# nRF24L01-Chip-v13.net
KiCad netlist of a schematic drawn in EAGLE
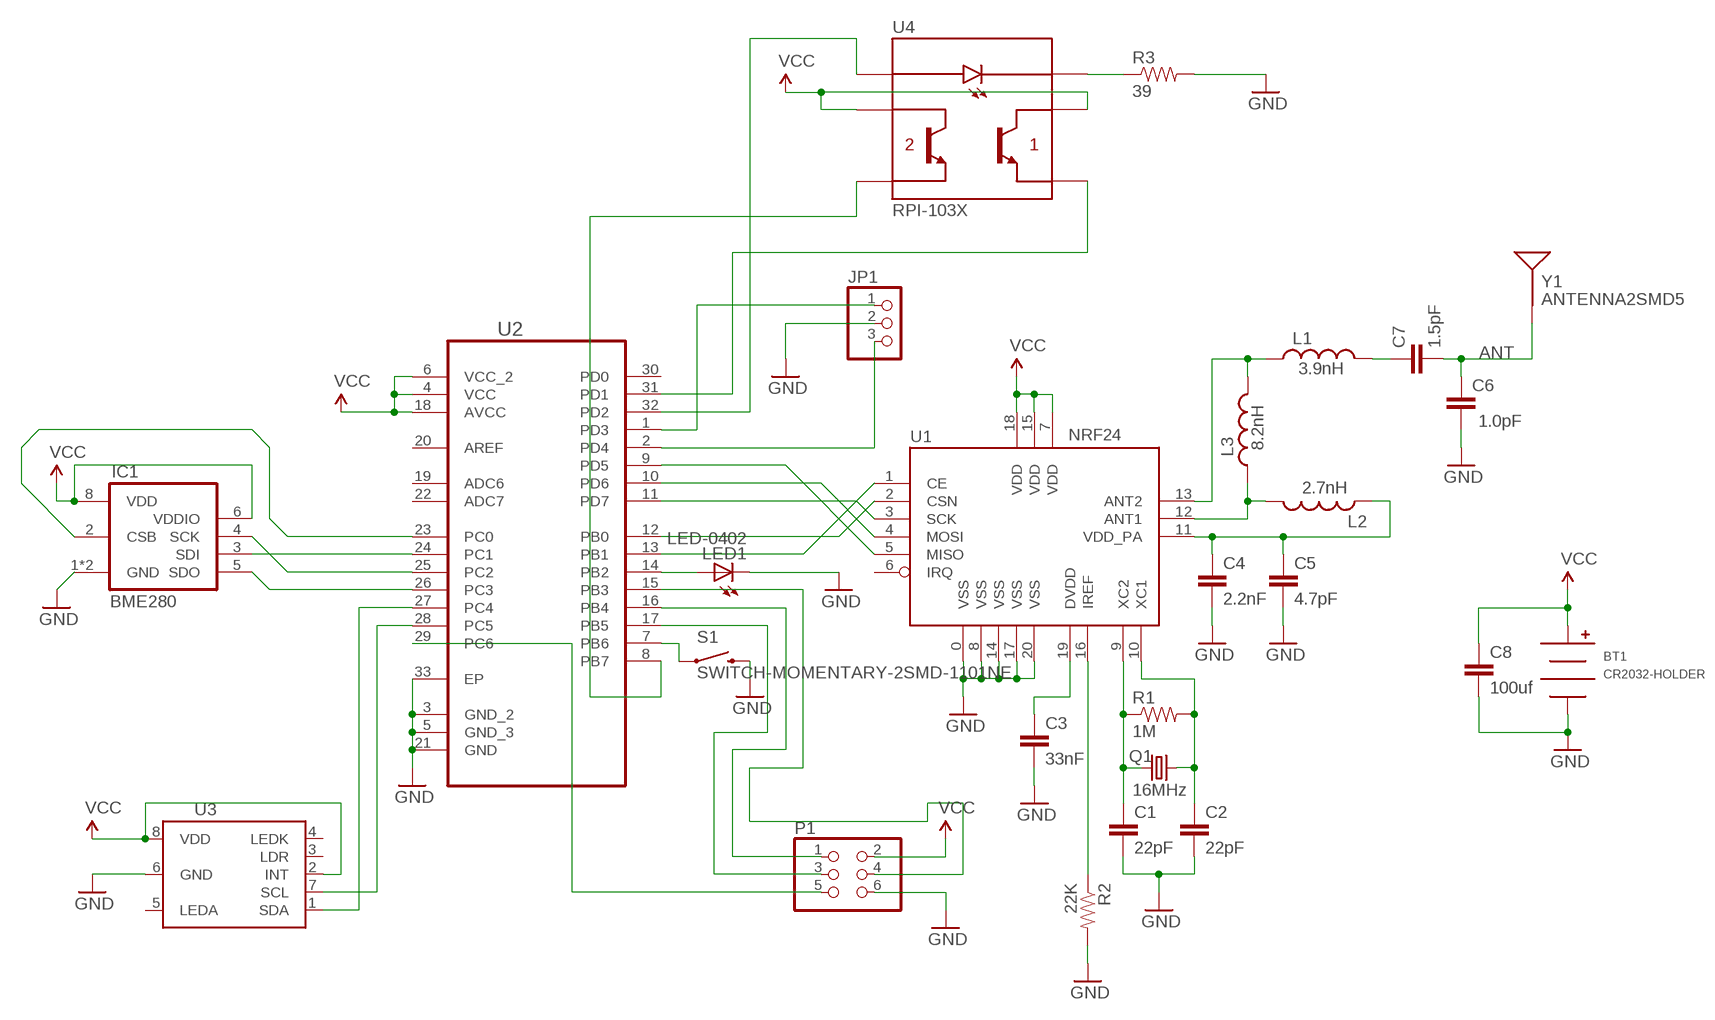
[diagram p0: schematic, sheet 1]

(export (version "E")
  (design (tool "Eeschema 10.0.6"))
  (components
    (comp (ref "BT1")
      (value "CR2032-HOLDER")
      (footprint "eagle-import:CH28-2032LF")
      (libsource (lib "eagle-import") (part "CR2032-HOLDER"))
    )
    (comp (ref "C1")
      (value "22pF")
      (footprint "eagle-import:0402-CAP")
      (libsource (lib "eagle-import") (part "CAP0402-CAP"))
    )
    (comp (ref "C2")
      (value "22pF")
      (footprint "eagle-import:0402-CAP")
      (libsource (lib "eagle-import") (part "CAP0402-CAP"))
    )
    (comp (ref "C3")
      (value "33nF")
      (footprint "eagle-import:0402-CAP")
      (libsource (lib "eagle-import") (part "CAP0402-CAP"))
    )
    (comp (ref "C4")
      (value "2.2nF")
      (footprint "eagle-import:0402-CAP")
      (libsource (lib "eagle-import") (part "CAP0402-CAP"))
    )
    (comp (ref "C5")
      (value "4.7pF")
      (footprint "eagle-import:0402-CAP")
      (libsource (lib "eagle-import") (part "CAP0402-CAP"))
    )
    (comp (ref "C6")
      (value "1.0pF")
      (footprint "eagle-import:0402-CAP")
      (libsource (lib "eagle-import") (part "CAP0402-CAP"))
    )
    (comp (ref "C7")
      (value "1.5pF")
      (footprint "eagle-import:0402-CAP")
      (libsource (lib "eagle-import") (part "CAP0402-CAP"))
    )
    (comp (ref "C8")
      (value "100uf")
      (footprint "eagle-import:1206")
      (libsource (lib "eagle-import") (part "SparkFun-Capacitors_CAP1206"))
    )
    (comp (ref "IC1")
      (value "BME280")
      (footprint "eagle-import:BME280")
      (libsource (lib "eagle-import") (part "BME280"))
    )
    (comp (ref "JP1")
      (value "PINHD-1X31X03_SMT")
      (footprint "eagle-import:1X03_SMT")
      (libsource (lib "eagle-import") (part "PINHD-1X31X03_SMT"))
    )
    (comp (ref "L1")
      (value "3.9nH")
      (footprint "eagle-import:C0402")
      (libsource (lib "eagle-import") (part "INDUCTOR0402"))
    )
    (comp (ref "L2")
      (value "2.7nH")
      (footprint "eagle-import:C0402")
      (libsource (lib "eagle-import") (part "INDUCTOR0402"))
    )
    (comp (ref "L3")
      (value "8.2nH")
      (footprint "eagle-import:C0402")
      (libsource (lib "eagle-import") (part "INDUCTOR0402"))
    )
    (comp (ref "LED1")
      (value "LED-0402")
      (footprint "eagle-import:0402-LED")
      (libsource (lib "eagle-import") (part "LED-0402"))
    )
    (comp (ref "P1")
      (value "PINHD-2X3SMT")
      (footprint "eagle-import:2X03_SMT")
      (libsource (lib "eagle-import") (part "PINHD-2X3SMT"))
    )
    (comp (ref "Q1")
      (value "16MHz")
      (footprint "eagle-import:CRYSTAL-SMD-5X3")
      (libsource (lib "eagle-import") (part "CRYSTAL5X3"))
    )
    (comp (ref "R1")
      (value "1M")
      (footprint "eagle-import:0402-RES")
      (libsource (lib "eagle-import") (part "RESISTOR0402-RES"))
    )
    (comp (ref "R2")
      (value "22K")
      (footprint "eagle-import:0402-RES")
      (libsource (lib "eagle-import") (part "RESISTOR0402-RES"))
    )
    (comp (ref "R3")
      (value "39")
      (footprint "eagle-import:0402-RES")
      (libsource (lib "eagle-import") (part "RESISTOR0402-RES"))
    )
    (comp (ref "S1")
      (value "SWITCH-MOMENTARY-2SMD-1101NE")
      (footprint "eagle-import:TACTILE-SWITCH-1101NE")
      (libsource (lib "eagle-import") (part "SWITCH-MOMENTARY-2SMD-1101NE"))
    )
    (comp (ref "U1")
      (value "NRF24")
      (footprint "eagle-import:QFN20_ALT1")
      (libsource (lib "eagle-import") (part "NRF24L01ALT1"))
    )
    (comp (ref "U2")
      (value "ATMEGA328P-MU")
      (footprint "eagle-import:QFN50P500X500X100-33N")
      (libsource (lib "eagle-import") (part "ATMEGA328P-MU"))
    )
    (comp (ref "U3")
      (value "APDS-9960")
      (footprint "eagle-import:APDS-9960")
      (libsource (lib "eagle-import") (part "APDS-9960"))
    )
    (comp (ref "U4")
      (value "RPI-103X")
      (footprint "eagle-import:RPI-103X")
      (libsource (lib "eagle-import") (part "RPI-103X"))
    )
    (comp (ref "Y1")
      (value "ANTENNA2SMD5")
      (footprint "eagle-import:ANTENNA-CHIP5")
      (libsource (lib "eagle-import") (part "ANTENNA2SMD5"))
    )
  )
  (nets
    (net (code "1") (name "/ANT") (class "Default")
      (node (ref "C6") (pin "2") (pinfunction "2_2") (pintype "passive"))
      (node (ref "C7") (pin "2") (pinfunction "2_2") (pintype "passive"))
      (node (ref "Y1") (pin "FEED") (pinfunction "SIGNAL_FEED") (pintype "bidirectional"))
    )
    (net (code "2") (name "GND") (class "Default")
      (node (ref "BT1") (pin "NEG") (pinfunction "NEG_NEG") (pintype "bidirectional"))
      (node (ref "C1") (pin "2") (pinfunction "2_2") (pintype "passive"))
      (node (ref "C2") (pin "2") (pinfunction "2_2") (pintype "passive"))
      (node (ref "C3") (pin "2") (pinfunction "2_2") (pintype "passive"))
      (node (ref "C4") (pin "2") (pinfunction "2_2") (pintype "passive"))
      (node (ref "C5") (pin "2") (pinfunction "2_2") (pintype "passive"))
      (node (ref "C6") (pin "1") (pinfunction "1_1") (pintype "passive"))
      (node (ref "C8") (pin "2") (pinfunction "2_2") (pintype "passive"))
      (node (ref "IC1") (pin "1") (pinfunction "GND_1") (pintype "power_in"))
      (node (ref "IC1") (pin "7") (pinfunction "GND_7") (pintype "power_in"))
      (node (ref "JP1") (pin "2") (pinfunction "2_2") (pintype "passive"))
      (node (ref "LED1") (pin "C") (pinfunction "C_C") (pintype "passive"))
      (node (ref "P1") (pin "6") (pinfunction "6_6") (pintype "passive"))
      (node (ref "R2") (pin "2") (pinfunction "2_2") (pintype "passive"))
      (node (ref "R3") (pin "2") (pinfunction "2_2") (pintype "passive"))
      (node (ref "S1") (pin "2") (pinfunction "2_2") (pintype "passive"))
      (node (ref "U1") (pin "0") (pinfunction "VSS_0") (pintype "power_in"))
      (node (ref "U1") (pin "14") (pinfunction "VSS_14") (pintype "power_in"))
      (node (ref "U1") (pin "17") (pinfunction "VSS_17") (pintype "power_in"))
      (node (ref "U1") (pin "20") (pinfunction "VSS_20") (pintype "power_in"))
      (node (ref "U1") (pin "8") (pinfunction "VSS_8") (pintype "power_in"))
      (node (ref "U2") (pin "21") (pinfunction "GND_21") (pintype "passive"))
      (node (ref "U2") (pin "3") (pinfunction "GND_2_3") (pintype "passive"))
      (node (ref "U2") (pin "33") (pinfunction "EP_33") (pintype "passive"))
      (node (ref "U2") (pin "5") (pinfunction "GND_3_5") (pintype "passive"))
      (node (ref "U3") (pin "6") (pinfunction "GND_6") (pintype "bidirectional"))
    )
    (net (code "3") (name "Net-(C7-Pad1)") (class "Default")
      (node (ref "C7") (pin "1") (pinfunction "1_1") (pintype "passive"))
      (node (ref "L1") (pin "2") (pinfunction "2_2") (pintype "passive"))
    )
    (net (code "4") (name "Net-(IC1-CSB)") (class "Default")
      (node (ref "IC1") (pin "2") (pinfunction "CSB_2") (pintype "input"))
      (node (ref "U2") (pin "23") (pinfunction "PC0_23") (pintype "bidirectional"))
    )
    (net (code "5") (name "Net-(IC1-SCK)") (class "Default")
      (node (ref "IC1") (pin "4") (pinfunction "SCK_4") (pintype "bidirectional"))
      (node (ref "U2") (pin "25") (pinfunction "PC2_25") (pintype "bidirectional"))
    )
    (net (code "6") (name "Net-(IC1-SDI)") (class "Default")
      (node (ref "IC1") (pin "3") (pinfunction "SDI_3") (pintype "bidirectional"))
      (node (ref "U2") (pin "24") (pinfunction "PC1_24") (pintype "bidirectional"))
    )
    (net (code "7") (name "Net-(IC1-SDO)") (class "Default")
      (node (ref "IC1") (pin "5") (pinfunction "SDO_5") (pintype "input"))
      (node (ref "U2") (pin "26") (pinfunction "PC3_26") (pintype "bidirectional"))
    )
    (net (code "8") (name "Net-(Q1-2)") (class "Default")
      (node (ref "C2") (pin "1") (pinfunction "1_1") (pintype "passive"))
      (node (ref "Q1") (pin "3") (pinfunction "2_3") (pintype "passive"))
      (node (ref "R1") (pin "2") (pinfunction "2_2") (pintype "passive"))
      (node (ref "U1") (pin "10") (pinfunction "XC1_10") (pintype "input"))
    )
    (net (code "9") (name "Net-(U1-ANT1)") (class "Default")
      (node (ref "L2") (pin "2") (pinfunction "2_2") (pintype "passive"))
      (node (ref "L3") (pin "1") (pinfunction "1_1") (pintype "passive"))
      (node (ref "U1") (pin "12") (pinfunction "ANT1_12") (pintype "output"))
    )
    (net (code "10") (name "Net-(U1-ANT2)") (class "Default")
      (node (ref "L1") (pin "1") (pinfunction "1_1") (pintype "passive"))
      (node (ref "L3") (pin "2") (pinfunction "2_2") (pintype "passive"))
      (node (ref "U1") (pin "13") (pinfunction "ANT2_13") (pintype "output"))
    )
    (net (code "11") (name "Net-(U1-CE)") (class "Default")
      (node (ref "U1") (pin "1") (pinfunction "CE_1") (pintype "input"))
      (node (ref "U2") (pin "13") (pinfunction "PB1_13") (pintype "bidirectional"))
    )
    (net (code "12") (name "Net-(U1-CSN)") (class "Default")
      (node (ref "U1") (pin "2") (pinfunction "CSN_2") (pintype "input"))
      (node (ref "U2") (pin "12") (pinfunction "PB0_12") (pintype "bidirectional"))
    )
    (net (code "13") (name "Net-(U1-DVDD)") (class "Default")
      (node (ref "C3") (pin "1") (pinfunction "1_1") (pintype "passive"))
      (node (ref "U1") (pin "19") (pinfunction "DVDD_19") (pintype "power_in"))
    )
    (net (code "14") (name "Net-(U1-IREF)") (class "Default")
      (node (ref "R2") (pin "1") (pinfunction "1_1") (pintype "passive"))
      (node (ref "U1") (pin "16") (pinfunction "IREF_16") (pintype "input"))
    )
    (net (code "15") (name "Net-(U1-MISO)") (class "Default")
      (node (ref "U1") (pin "5") (pinfunction "MISO_5") (pintype "output"))
      (node (ref "U2") (pin "9") (pinfunction "PD5_9") (pintype "bidirectional"))
    )
    (net (code "16") (name "Net-(U1-MOSI)") (class "Default")
      (node (ref "U1") (pin "4") (pinfunction "MOSI_4") (pintype "input"))
      (node (ref "U2") (pin "10") (pinfunction "PD6_10") (pintype "bidirectional"))
    )
    (net (code "17") (name "Net-(U1-SCK)") (class "Default")
      (node (ref "U1") (pin "3") (pinfunction "SCK_3") (pintype "input"))
      (node (ref "U2") (pin "11") (pinfunction "PD7_11") (pintype "bidirectional"))
    )
    (net (code "18") (name "Net-(U1-VDD_PA)") (class "Default")
      (node (ref "C4") (pin "1") (pinfunction "1_1") (pintype "passive"))
      (node (ref "C5") (pin "1") (pinfunction "1_1") (pintype "passive"))
      (node (ref "L2") (pin "1") (pinfunction "1_1") (pintype "passive"))
      (node (ref "U1") (pin "11") (pinfunction "VDD_PA_11") (pintype "power_in"))
    )
    (net (code "19") (name "Net-(U1-XC2)") (class "Default")
      (node (ref "C1") (pin "1") (pinfunction "1_1") (pintype "passive"))
      (node (ref "Q1") (pin "1") (pinfunction "1_1") (pintype "passive"))
      (node (ref "R1") (pin "1") (pinfunction "1_1") (pintype "passive"))
      (node (ref "U1") (pin "9") (pinfunction "XC2_9") (pintype "input"))
    )
    (net (code "20") (name "Net-(U2-PB2)") (class "Default")
      (node (ref "LED1") (pin "A") (pinfunction "A_A") (pintype "passive"))
      (node (ref "U2") (pin "14") (pinfunction "PB2_14") (pintype "bidirectional"))
    )
    (net (code "21") (name "Net-(U2-PB3)") (class "Default")
      (node (ref "P1") (pin "4") (pinfunction "4_4") (pintype "passive"))
      (node (ref "U2") (pin "15") (pinfunction "PB3_15") (pintype "bidirectional"))
    )
    (net (code "22") (name "Net-(U2-PB4)") (class "Default")
      (node (ref "P1") (pin "1") (pinfunction "1_1") (pintype "passive"))
      (node (ref "U2") (pin "16") (pinfunction "PB4_16") (pintype "bidirectional"))
    )
    (net (code "23") (name "Net-(U2-PB5)") (class "Default")
      (node (ref "P1") (pin "3") (pinfunction "3_3") (pintype "passive"))
      (node (ref "U2") (pin "17") (pinfunction "PB5_17") (pintype "bidirectional"))
    )
    (net (code "24") (name "Net-(U2-PB6)") (class "Default")
      (node (ref "S1") (pin "1") (pinfunction "1_1") (pintype "passive"))
      (node (ref "U2") (pin "7") (pinfunction "PB6_7") (pintype "bidirectional"))
    )
    (net (code "25") (name "Net-(U2-PB7)") (class "Default")
      (node (ref "U2") (pin "8") (pinfunction "PB7_8") (pintype "bidirectional"))
      (node (ref "U4") (pin "4") (pinfunction "E2_4") (pintype "passive"))
    )
    (net (code "26") (name "Net-(U2-PC4)") (class "Default")
      (node (ref "U2") (pin "27") (pinfunction "PC4_27") (pintype "bidirectional"))
      (node (ref "U3") (pin "1") (pinfunction "SDA_1") (pintype "bidirectional"))
    )
    (net (code "27") (name "Net-(U2-PC5)") (class "Default")
      (node (ref "U2") (pin "28") (pinfunction "PC5_28") (pintype "bidirectional"))
      (node (ref "U3") (pin "7") (pinfunction "SCL_7") (pintype "bidirectional"))
    )
    (net (code "28") (name "Net-(U2-PC6)") (class "Default")
      (node (ref "P1") (pin "5") (pinfunction "5_5") (pintype "passive"))
      (node (ref "U2") (pin "29") (pinfunction "PC6_29") (pintype "bidirectional"))
    )
    (net (code "29") (name "Net-(U2-PD1)") (class "Default")
      (node (ref "U2") (pin "31") (pinfunction "PD1_31") (pintype "bidirectional"))
      (node (ref "U4") (pin "1") (pinfunction "E1_1") (pintype "passive"))
    )
    (net (code "30") (name "Net-(U2-PD2)") (class "Default")
      (node (ref "U2") (pin "32") (pinfunction "PD2_32") (pintype "bidirectional"))
      (node (ref "U4") (pin "6") (pinfunction "ANODE_6") (pintype "passive"))
    )
    (net (code "31") (name "Net-(U2-PD3)") (class "Default")
      (node (ref "JP1") (pin "1") (pinfunction "1_1") (pintype "passive"))
      (node (ref "U2") (pin "1") (pinfunction "PD3_1") (pintype "bidirectional"))
    )
    (net (code "32") (name "Net-(U2-PD4)") (class "Default")
      (node (ref "JP1") (pin "3") (pinfunction "3_3") (pintype "passive"))
      (node (ref "U2") (pin "2") (pinfunction "PD4_2") (pintype "bidirectional"))
    )
    (net (code "33") (name "Net-(U4-CATHODE)") (class "Default")
      (node (ref "R3") (pin "1") (pinfunction "1_1") (pintype "passive"))
      (node (ref "U4") (pin "3") (pinfunction "CATHODE_3") (pintype "passive"))
    )
    (net (code "34") (name "VCC") (class "Default")
      (node (ref "BT1") (pin "POS") (pinfunction "POS_POS") (pintype "bidirectional"))
      (node (ref "C8") (pin "1") (pinfunction "1_1") (pintype "passive"))
      (node (ref "IC1") (pin "6") (pinfunction "VDDIO_6") (pintype "power_in"))
      (node (ref "IC1") (pin "8") (pinfunction "VDD_8") (pintype "power_in"))
      (node (ref "P1") (pin "2") (pinfunction "2_2") (pintype "passive"))
      (node (ref "U1") (pin "15") (pinfunction "VDD_15") (pintype "power_in"))
      (node (ref "U1") (pin "18") (pinfunction "VDD_18") (pintype "power_in"))
      (node (ref "U1") (pin "7") (pinfunction "VDD_7") (pintype "power_in"))
      (node (ref "U2") (pin "18") (pinfunction "AVCC_18") (pintype "power_in"))
      (node (ref "U2") (pin "4") (pinfunction "VCC_4") (pintype "power_in"))
      (node (ref "U2") (pin "6") (pinfunction "VCC_2_6") (pintype "power_in"))
      (node (ref "U3") (pin "2") (pinfunction "INT_2") (pintype "bidirectional"))
      (node (ref "U3") (pin "8") (pinfunction "VDD_8") (pintype "bidirectional"))
      (node (ref "U4") (pin "2") (pinfunction "C1_2") (pintype "passive"))
      (node (ref "U4") (pin "5") (pinfunction "C2_5") (pintype "passive"))
    )
    (net (code "35") (name "unconnected-(U1-IRQ-Pad6)") (class "Default")
      (node (ref "U1") (pin "6") (pinfunction "IRQ_6") (pintype "output"))
    )
    (net (code "36") (name "unconnected-(U2-ADC6-Pad19)") (class "Default")
      (node (ref "U2") (pin "19") (pinfunction "ADC6_19") (pintype "input"))
    )
    (net (code "37") (name "unconnected-(U2-ADC7-Pad22)") (class "Default")
      (node (ref "U2") (pin "22") (pinfunction "ADC7_22") (pintype "input"))
    )
    (net (code "38") (name "unconnected-(U2-AREF-Pad20)") (class "Default")
      (node (ref "U2") (pin "20") (pinfunction "AREF_20") (pintype "input"))
    )
    (net (code "39") (name "unconnected-(U2-PD0-Pad30)") (class "Default")
      (node (ref "U2") (pin "30") (pinfunction "PD0_30") (pintype "bidirectional"))
    )
    (net (code "40") (name "unconnected-(U3-LDR-Pad3)") (class "Default")
      (node (ref "U3") (pin "3") (pinfunction "LDR_3") (pintype "bidirectional"))
    )
    (net (code "41") (name "unconnected-(U3-LEDA-Pad5)") (class "Default")
      (node (ref "U3") (pin "5") (pinfunction "LEDA_5") (pintype "bidirectional"))
    )
    (net (code "42") (name "unconnected-(U3-LEDK-Pad4)") (class "Default")
      (node (ref "U3") (pin "4") (pinfunction "LEDK_4") (pintype "bidirectional"))
    )
  )
)
